# Open_close_Lid.net
KiCad netlist of a schematic drawn in EAGLE
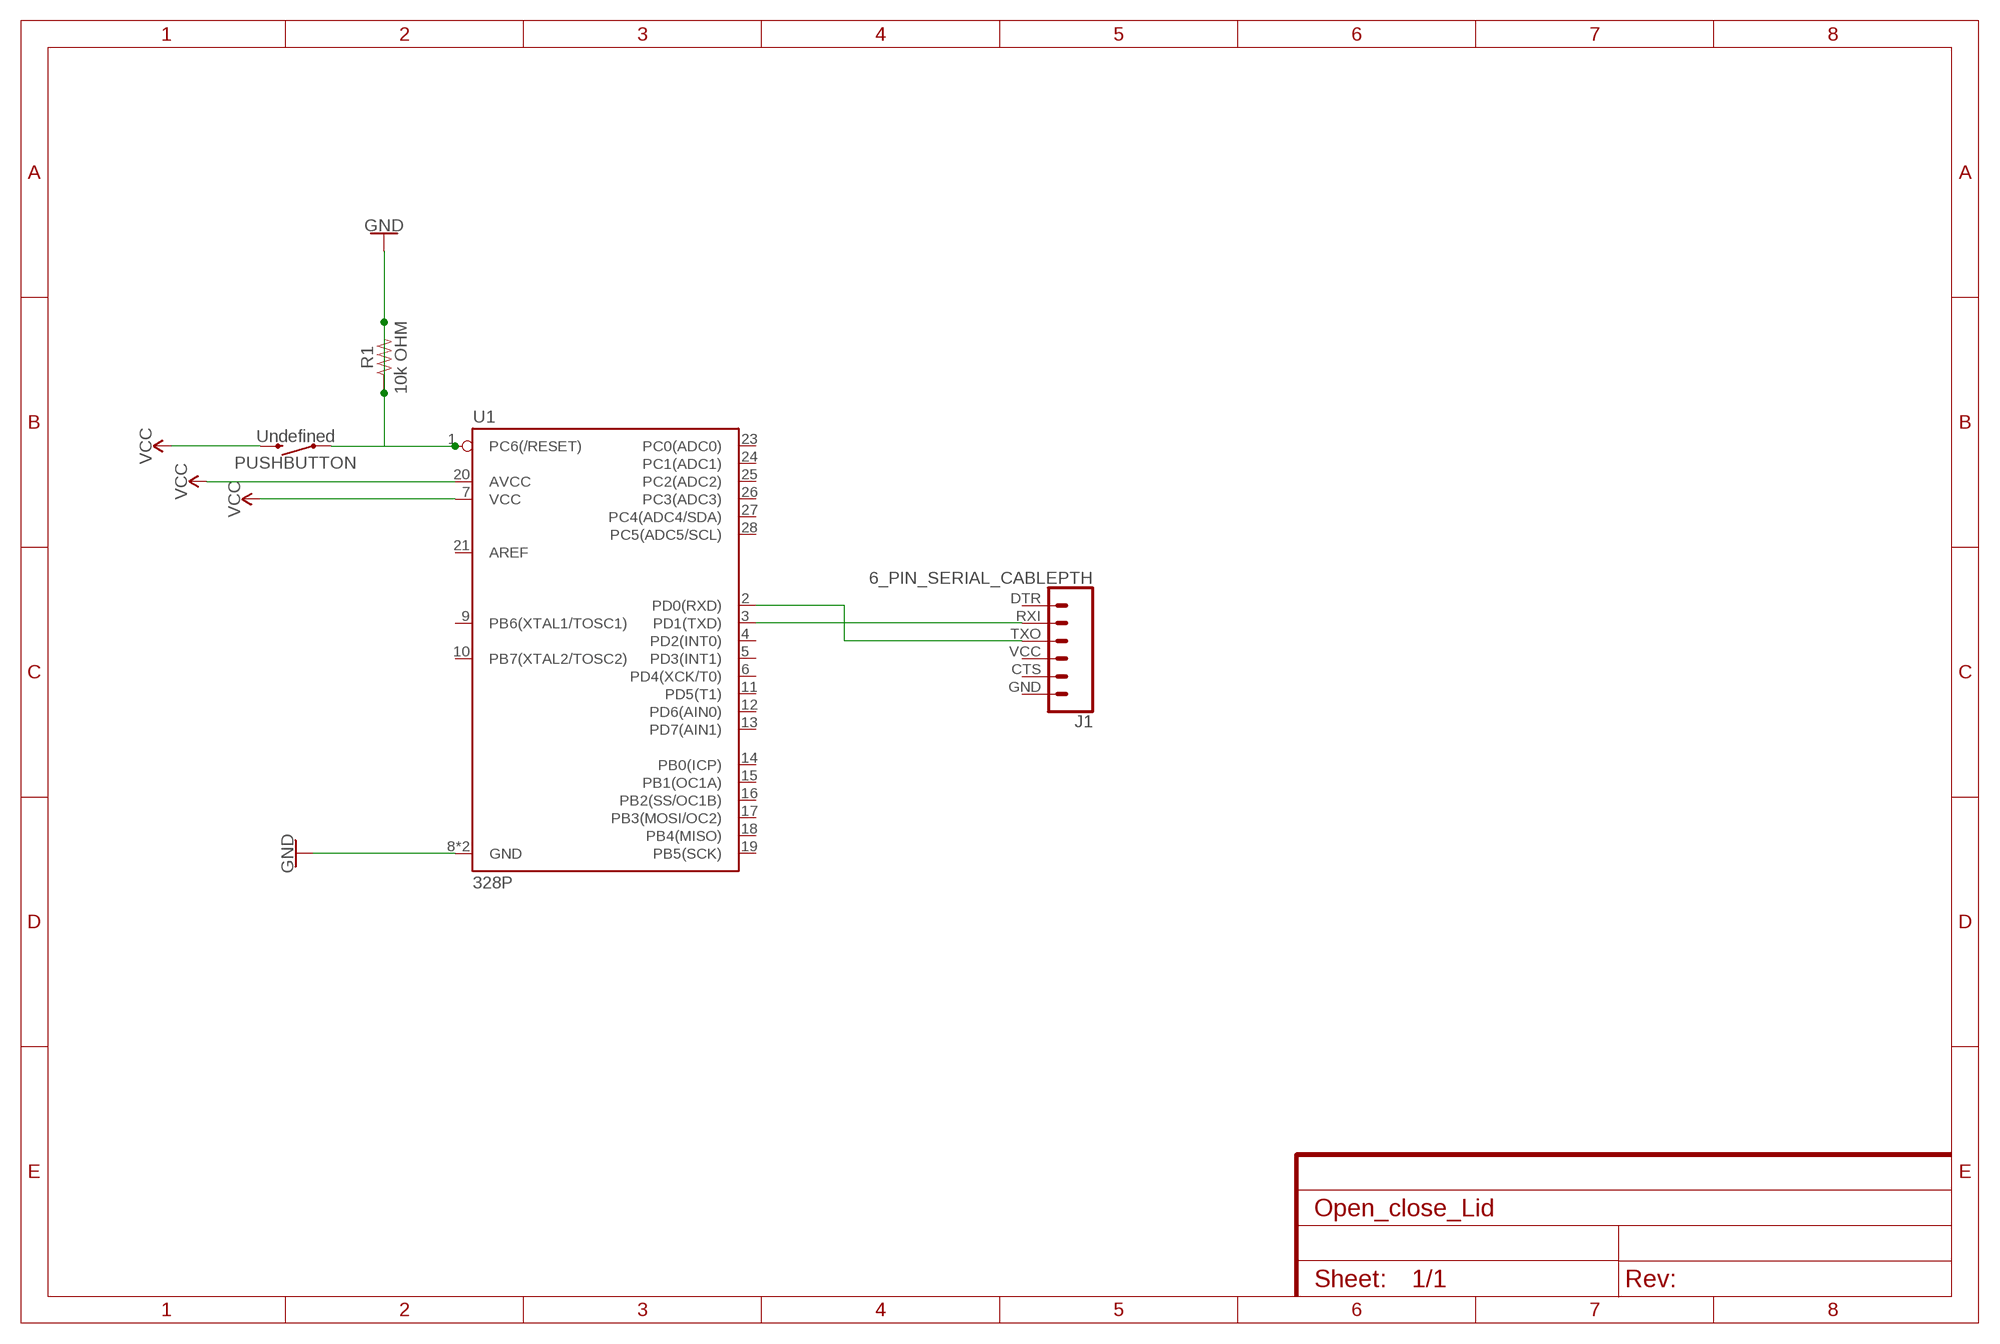
[diagram p0: schematic, sheet 1]

(export (version "E")
  (design (tool "Eeschema 10.0.6"))
  (components
    (comp (ref "J1")
      (value "6_PIN_SERIAL_CABLEPTH")
      (footprint "eagle-import:FTDI_BASIC")
      (libsource (lib "eagle-import") (part "6_PIN_SERIAL_CABLEPTH"))
    )
    (comp (ref "PUSHBUTTON")
      (value "Undefined")
      (footprint "eagle-import:TACTILE_SWITCH_PTH_6.0MM")
      (libsource (lib "eagle-import") (part "MOMENTARY-SWITCH-SPST-PTH-6.0MM"))
    )
    (comp (ref "R1")
      (value "10k OHM")
      (footprint "eagle-import:AXIAL-0.3")
      (libsource (lib "eagle-import") (part "10KOHM-HORIZ-1/4W-1%"))
    )
    (comp (ref "U1")
      (value "328P")
      (footprint "eagle-import:DIP28")
      (libsource (lib "eagle-import") (part "ATMEGA328P_PDIP"))
    )
  )
  (nets
    (net (code "1") (name "GND") (class "Default")
      (node (ref "PUSHBUTTON") (pin "1") (pinfunction "1_1") (pintype "passive"))
      (node (ref "R1") (pin "P$1") (pinfunction "1_P$1") (pintype "passive"))
      (node (ref "R1") (pin "P$2") (pinfunction "2_P$2") (pintype "passive"))
      (node (ref "U1") (pin "1") (pinfunction "PC6(/RESET)_1") (pintype "bidirectional"))
      (node (ref "U1") (pin "22") (pinfunction "GND_22") (pintype "bidirectional"))
      (node (ref "U1") (pin "8") (pinfunction "GND_8") (pintype "bidirectional"))
    )
    (net (code "2") (name "Net-(J1-2)") (class "Default")
      (node (ref "J1") (pin "RXI") (pinfunction "2_RXI") (pintype "passive"))
      (node (ref "U1") (pin "3") (pinfunction "PD1(TXD)_3") (pintype "bidirectional"))
    )
    (net (code "3") (name "Net-(J1-3)") (class "Default")
      (node (ref "J1") (pin "TXO") (pinfunction "3_TXO") (pintype "passive"))
      (node (ref "U1") (pin "2") (pinfunction "PD0(RXD)_2") (pintype "bidirectional"))
    )
    (net (code "4") (name "VCC") (class "Default")
      (node (ref "PUSHBUTTON") (pin "3") (pinfunction "2_3") (pintype "passive"))
      (node (ref "U1") (pin "20") (pinfunction "AVCC_20") (pintype "bidirectional"))
      (node (ref "U1") (pin "7") (pinfunction "VCC_7") (pintype "bidirectional"))
    )
    (net (code "5") (name "unconnected-(J1-1-PadDTR)") (class "Default")
      (node (ref "J1") (pin "DTR") (pinfunction "1_DTR") (pintype "passive"))
    )
    (net (code "6") (name "unconnected-(J1-4-PadVCC)") (class "Default")
      (node (ref "J1") (pin "VCC") (pinfunction "4_VCC") (pintype "passive"))
    )
    (net (code "7") (name "unconnected-(J1-5-PadCTS)") (class "Default")
      (node (ref "J1") (pin "CTS") (pinfunction "5_CTS") (pintype "passive"))
    )
    (net (code "8") (name "unconnected-(J1-6-PadGND)") (class "Default")
      (node (ref "J1") (pin "GND") (pinfunction "6_GND") (pintype "passive"))
    )
    (net (code "9") (name "unconnected-(U1-AREF-Pad21)") (class "Default")
      (node (ref "U1") (pin "21") (pinfunction "AREF_21") (pintype "bidirectional"))
    )
    (net (code "10") (name "unconnected-(U1-PB0(ICP)-Pad14)") (class "Default")
      (node (ref "U1") (pin "14") (pinfunction "PB0(ICP)_14") (pintype "bidirectional"))
    )
    (net (code "11") (name "unconnected-(U1-PB1(OC1A)-Pad15)") (class "Default")
      (node (ref "U1") (pin "15") (pinfunction "PB1(OC1A)_15") (pintype "bidirectional"))
    )
    (net (code "12") (name "unconnected-(U1-PB2(SS{slash}OC1B)-Pad16)") (class "Default")
      (node (ref "U1") (pin "16") (pinfunction "PB2(SS/OC1B)_16") (pintype "bidirectional"))
    )
    (net (code "13") (name "unconnected-(U1-PB3(MOSI{slash}OC2)-Pad17)") (class "Default")
      (node (ref "U1") (pin "17") (pinfunction "PB3(MOSI/OC2)_17") (pintype "bidirectional"))
    )
    (net (code "14") (name "unconnected-(U1-PB4(MISO)-Pad18)") (class "Default")
      (node (ref "U1") (pin "18") (pinfunction "PB4(MISO)_18") (pintype "bidirectional"))
    )
    (net (code "15") (name "unconnected-(U1-PB5(SCK)-Pad19)") (class "Default")
      (node (ref "U1") (pin "19") (pinfunction "PB5(SCK)_19") (pintype "bidirectional"))
    )
    (net (code "16") (name "unconnected-(U1-PB6(XTAL1{slash}TOSC1)-Pad9)") (class "Default")
      (node (ref "U1") (pin "9") (pinfunction "PB6(XTAL1/TOSC1)_9") (pintype "bidirectional"))
    )
    (net (code "17") (name "unconnected-(U1-PB7(XTAL2{slash}TOSC2)-Pad10)") (class "Default")
      (node (ref "U1") (pin "10") (pinfunction "PB7(XTAL2/TOSC2)_10") (pintype "bidirectional"))
    )
    (net (code "18") (name "unconnected-(U1-PC0(ADC0)-Pad23)") (class "Default")
      (node (ref "U1") (pin "23") (pinfunction "PC0(ADC0)_23") (pintype "bidirectional"))
    )
    (net (code "19") (name "unconnected-(U1-PC1(ADC1)-Pad24)") (class "Default")
      (node (ref "U1") (pin "24") (pinfunction "PC1(ADC1)_24") (pintype "bidirectional"))
    )
    (net (code "20") (name "unconnected-(U1-PC2(ADC2)-Pad25)") (class "Default")
      (node (ref "U1") (pin "25") (pinfunction "PC2(ADC2)_25") (pintype "bidirectional"))
    )
    (net (code "21") (name "unconnected-(U1-PC3(ADC3)-Pad26)") (class "Default")
      (node (ref "U1") (pin "26") (pinfunction "PC3(ADC3)_26") (pintype "bidirectional"))
    )
    (net (code "22") (name "unconnected-(U1-PC4(ADC4{slash}SDA)-Pad27)") (class "Default")
      (node (ref "U1") (pin "27") (pinfunction "PC4(ADC4/SDA)_27") (pintype "bidirectional"))
    )
    (net (code "23") (name "unconnected-(U1-PC5(ADC5{slash}SCL)-Pad28)") (class "Default")
      (node (ref "U1") (pin "28") (pinfunction "PC5(ADC5/SCL)_28") (pintype "bidirectional"))
    )
    (net (code "24") (name "unconnected-(U1-PD2(INT0)-Pad4)") (class "Default")
      (node (ref "U1") (pin "4") (pinfunction "PD2(INT0)_4") (pintype "bidirectional"))
    )
    (net (code "25") (name "unconnected-(U1-PD3(INT1)-Pad5)") (class "Default")
      (node (ref "U1") (pin "5") (pinfunction "PD3(INT1)_5") (pintype "bidirectional"))
    )
    (net (code "26") (name "unconnected-(U1-PD4(XCK{slash}T0)-Pad6)") (class "Default")
      (node (ref "U1") (pin "6") (pinfunction "PD4(XCK/T0)_6") (pintype "bidirectional"))
    )
    (net (code "27") (name "unconnected-(U1-PD5(T1)-Pad11)") (class "Default")
      (node (ref "U1") (pin "11") (pinfunction "PD5(T1)_11") (pintype "bidirectional"))
    )
    (net (code "28") (name "unconnected-(U1-PD6(AIN0)-Pad12)") (class "Default")
      (node (ref "U1") (pin "12") (pinfunction "PD6(AIN0)_12") (pintype "bidirectional"))
    )
    (net (code "29") (name "unconnected-(U1-PD7(AIN1)-Pad13)") (class "Default")
      (node (ref "U1") (pin "13") (pinfunction "PD7(AIN1)_13") (pintype "bidirectional"))
    )
  )
)
